# 12_LED_Ring.net
KiCad netlist of a schematic drawn in EAGLE
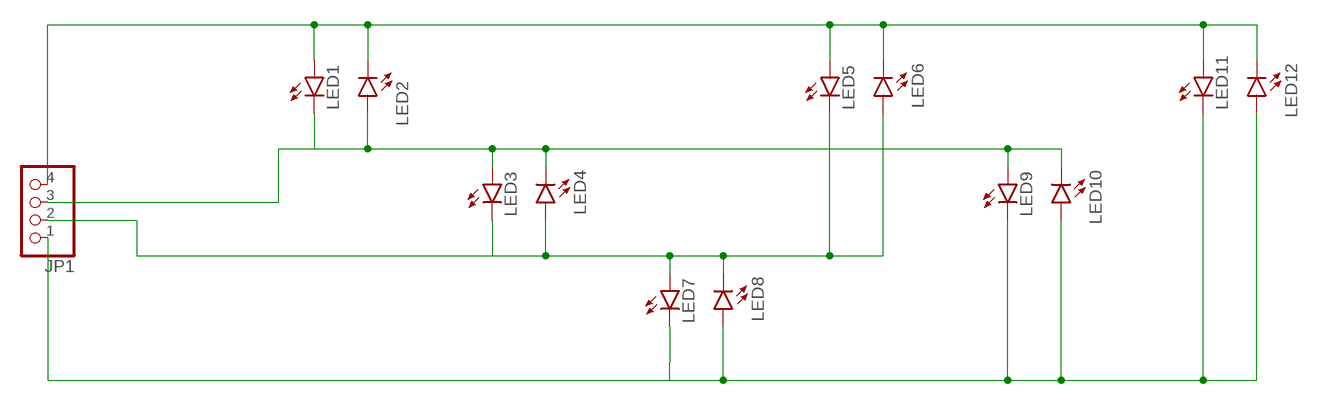
[diagram p0: schematic, sheet 1]

(export (version "E")
  (design (tool "Eeschema 10.0.6"))
  (components
    (comp (ref "JP1")
      (value "PINHD-1X4")
      (footprint "eagle-import:1X04")
      (libsource (lib "eagle-import") (part "PINHD-1X4"))
    )
    (comp (ref "LED1")
      (value "LED5MM")
      (footprint "eagle-import:LED5MM")
      (libsource (lib "eagle-import") (part "LED5MM"))
    )
    (comp (ref "LED2")
      (value "LED5MM")
      (footprint "eagle-import:LED5MM")
      (libsource (lib "eagle-import") (part "LED5MM"))
    )
    (comp (ref "LED3")
      (value "LED5MM")
      (footprint "eagle-import:LED5MM")
      (libsource (lib "eagle-import") (part "LED5MM"))
    )
    (comp (ref "LED4")
      (value "LED5MM")
      (footprint "eagle-import:LED5MM")
      (libsource (lib "eagle-import") (part "LED5MM"))
    )
    (comp (ref "LED5")
      (value "LED5MM")
      (footprint "eagle-import:LED5MM")
      (libsource (lib "eagle-import") (part "LED5MM"))
    )
    (comp (ref "LED6")
      (value "LED5MM")
      (footprint "eagle-import:LED5MM")
      (libsource (lib "eagle-import") (part "LED5MM"))
    )
    (comp (ref "LED7")
      (value "LED5MM")
      (footprint "eagle-import:LED5MM")
      (libsource (lib "eagle-import") (part "LED5MM"))
    )
    (comp (ref "LED8")
      (value "LED5MM")
      (footprint "eagle-import:LED5MM")
      (libsource (lib "eagle-import") (part "LED5MM"))
    )
    (comp (ref "LED9")
      (value "LED5MM")
      (footprint "eagle-import:LED5MM")
      (libsource (lib "eagle-import") (part "LED5MM"))
    )
    (comp (ref "LED10")
      (value "LED5MM")
      (footprint "eagle-import:LED5MM")
      (libsource (lib "eagle-import") (part "LED5MM"))
    )
    (comp (ref "LED11")
      (value "LED5MM")
      (footprint "eagle-import:LED5MM")
      (libsource (lib "eagle-import") (part "LED5MM"))
    )
    (comp (ref "LED12")
      (value "LED5MM")
      (footprint "eagle-import:LED5MM")
      (libsource (lib "eagle-import") (part "LED5MM"))
    )
  )
  (nets
    (net (code "1") (name "Net-(LED1-C)") (class "Default")
      (node (ref "JP1") (pin "3") (pinfunction "3_3") (pintype "passive"))
      (node (ref "LED1") (pin "K") (pinfunction "C_K") (pintype "passive"))
      (node (ref "LED10") (pin "K") (pinfunction "C_K") (pintype "passive"))
      (node (ref "LED2") (pin "A") (pinfunction "A_A") (pintype "passive"))
      (node (ref "LED3") (pin "A") (pinfunction "A_A") (pintype "passive"))
      (node (ref "LED4") (pin "K") (pinfunction "C_K") (pintype "passive"))
      (node (ref "LED9") (pin "A") (pinfunction "A_A") (pintype "passive"))
    )
    (net (code "2") (name "Net-(LED3-C)") (class "Default")
      (node (ref "JP1") (pin "2") (pinfunction "2_2") (pintype "passive"))
      (node (ref "LED3") (pin "K") (pinfunction "C_K") (pintype "passive"))
      (node (ref "LED4") (pin "A") (pinfunction "A_A") (pintype "passive"))
      (node (ref "LED5") (pin "K") (pinfunction "C_K") (pintype "passive"))
      (node (ref "LED6") (pin "A") (pinfunction "A_A") (pintype "passive"))
      (node (ref "LED7") (pin "A") (pinfunction "A_A") (pintype "passive"))
      (node (ref "LED8") (pin "K") (pinfunction "C_K") (pintype "passive"))
    )
    (net (code "3") (name "Net-(LED11-C)") (class "Default")
      (node (ref "JP1") (pin "1") (pinfunction "1_1") (pintype "passive"))
      (node (ref "LED10") (pin "A") (pinfunction "A_A") (pintype "passive"))
      (node (ref "LED11") (pin "K") (pinfunction "C_K") (pintype "passive"))
      (node (ref "LED12") (pin "A") (pinfunction "A_A") (pintype "passive"))
      (node (ref "LED7") (pin "K") (pinfunction "C_K") (pintype "passive"))
      (node (ref "LED8") (pin "A") (pinfunction "A_A") (pintype "passive"))
      (node (ref "LED9") (pin "K") (pinfunction "C_K") (pintype "passive"))
    )
    (net (code "4") (name "Net-(LED12-C)") (class "Default")
      (node (ref "JP1") (pin "4") (pinfunction "4_4") (pintype "passive"))
      (node (ref "LED1") (pin "A") (pinfunction "A_A") (pintype "passive"))
      (node (ref "LED11") (pin "A") (pinfunction "A_A") (pintype "passive"))
      (node (ref "LED12") (pin "K") (pinfunction "C_K") (pintype "passive"))
      (node (ref "LED2") (pin "K") (pinfunction "C_K") (pintype "passive"))
      (node (ref "LED5") (pin "A") (pinfunction "A_A") (pintype "passive"))
      (node (ref "LED6") (pin "K") (pinfunction "C_K") (pintype "passive"))
    )
  )
)
